# EthernetSwitchBoard.net
KiCad netlist of a schematic drawn in Altium Designer
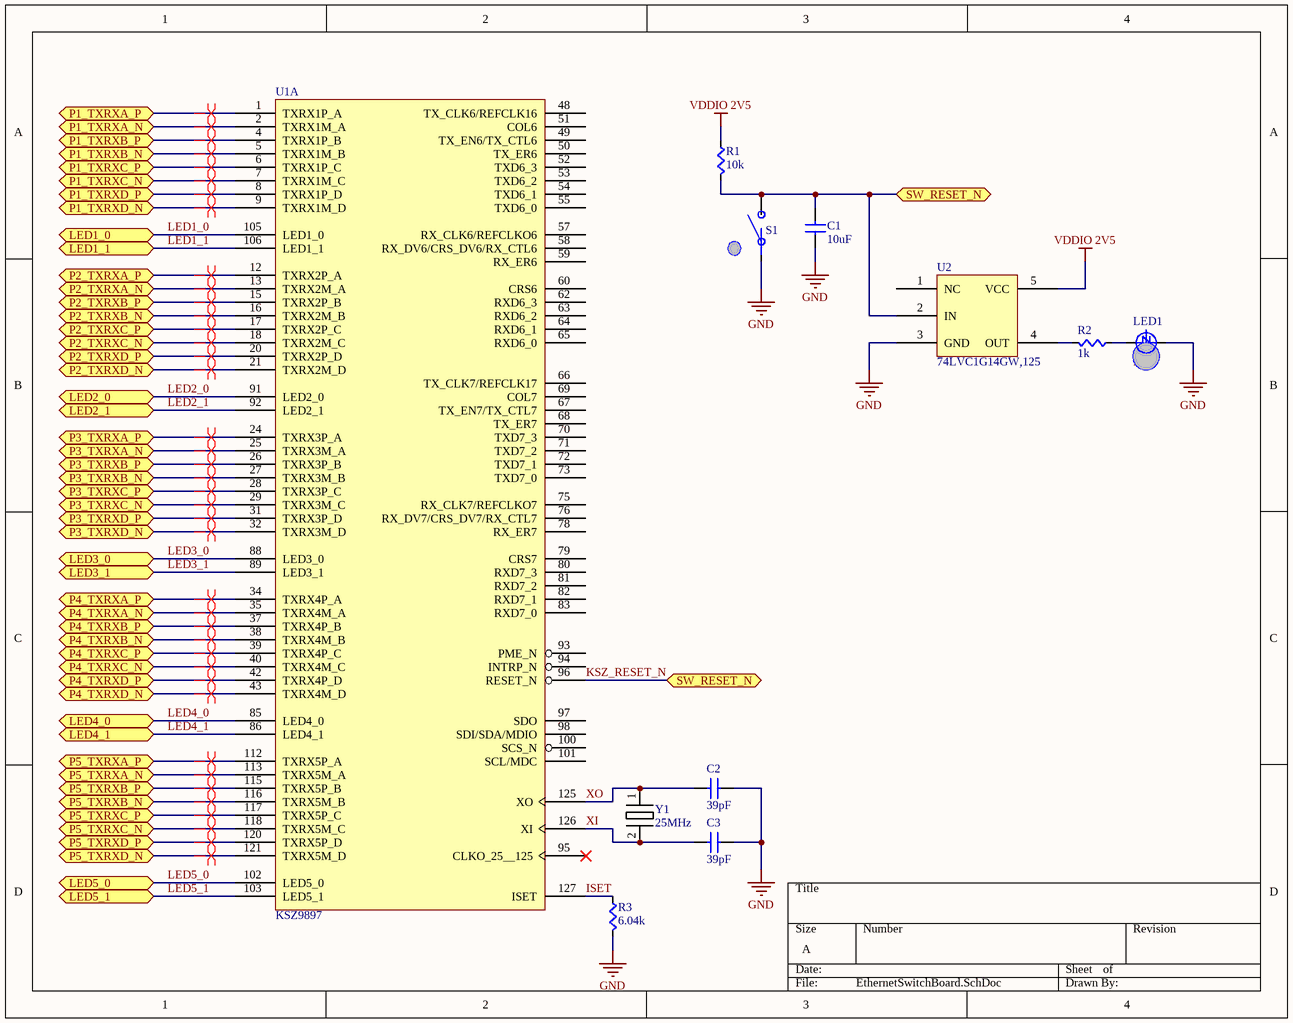
[diagram p0: EthernetSwitchBoard.SchDoc]

(export (version "E")
  (design (tool "Eeschema 10.0.6"))
  (components
    (comp (ref "C1")
      (value "10uF")
      (footprint "CAPC0603")
      (fields (field (name "Comment") "Cap"))
      (libsource (lib "Passives") (part "Cap"))
    )
    (comp (ref "C2")
      (value "39pF")
      (footprint "CAPC0603")
      (description "CAP CER 39PF 100V C0G/NP0 0603")
      (fields (field (name "Comment") "Cap"))
      (libsource (lib "Passives") (part "Cap"))
    )
    (comp (ref "C3")
      (value "39pF")
      (footprint "CAPC0603")
      (description "CAP CER 39PF 100V C0G/NP0 0603")
      (fields (field (name "Comment") "Cap"))
      (libsource (lib "Passives") (part "Cap"))
    )
    (comp (ref "LED1")
      (value "LED")
      (footprint "LED0603")
      (fields (field (name "COLOR") "Red"))
      (libsource (lib "Semiconductors") (part "LED"))
    )
    (comp (ref "R1")
      (value "10k")
      (footprint "RES0603")
      (fields (field (name "Comment") "Res"))
      (libsource (lib "Passives") (part "Res"))
    )
    (comp (ref "R2")
      (value "1k")
      (footprint "RES0603")
      (fields (field (name "Comment") "Res"))
      (libsource (lib "Passives") (part "Res"))
    )
    (comp (ref "R3")
      (value "6.04k")
      (footprint "RES0603")
      (fields (field (name "Comment") "Res"))
      (libsource (lib "Passives") (part "Res"))
    )
    (comp (ref "S1")
      (value "Button")
      (footprint "PTS645xxxxSMTR92")
      (description "SPST Button")
      (libsource (lib "Passives") (part "Button"))
    )
    (comp (ref "U1")
      (value "KSZ9897")
      (footprint "ICs:128-TQFP")
      (description "Ethernet Switch 10/100/1000 Base-T PHY I²C, SPI Interface 128-TQFP (14x14)")
      (libsource (lib "ICs") (part "KSZ9897RTXC-TR"))
    )
    (comp (ref "U2")
      (value "74LVC1G14GW,125")
      (footprint "ICs:SOT35-5pin")
      (description "IC SCHMITT-TRIG INV 5TSSOP")
      (libsource (lib "ICs") (part "74LVC1G14GW,125"))
    )
    (comp (ref "Y1")
      (value "25MHz")
      (footprint "ICs:HC49/US")
      (description "25MHz ±30ppm Crystal 18pF 40 Ohm -20°C ~ 70°C Surface Mount HC49/US")
      (libsource (lib "ICs") (part "ABLS-25.000MHZ-B4-F-T"))
    )
  )
  (nets
    (net (code "1") (name "/ISET") (class "Default")
      (node (ref "R3") (pin "2") (pinfunction "B_2") (pintype "passive"))
      (node (ref "U1") (pin "127") (pinfunction "ISET_127") (pintype "passive"))
    )
    (net (code "2") (name "/KSZ_RESET_N") (class "Default")
      (node (ref "C1") (pin "1") (pinfunction "A_1") (pintype "passive"))
      (node (ref "R1") (pin "1") (pinfunction "A_1") (pintype "passive"))
      (node (ref "S1") (pin "B") (pinfunction "B_B") (pintype "passive"))
      (node (ref "U1") (pin "96") (pinfunction "RESET_N_96") (pintype "passive"))
      (node (ref "U2") (pin "2") (pinfunction "IN_2") (pintype "passive"))
    )
    (net (code "3") (name "/LED1_0") (class "Default")
      (node (ref "U1") (pin "105") (pinfunction "LED1_0_105") (pintype "passive"))
    )
    (net (code "4") (name "/LED1_1") (class "Default")
      (node (ref "U1") (pin "106") (pinfunction "LED1_1_106") (pintype "passive"))
    )
    (net (code "5") (name "/LED2_0") (class "Default")
      (node (ref "U1") (pin "91") (pinfunction "LED2_0_91") (pintype "passive"))
    )
    (net (code "6") (name "/LED2_1") (class "Default")
      (node (ref "U1") (pin "92") (pinfunction "LED2_1_92") (pintype "passive"))
    )
    (net (code "7") (name "/LED3_0") (class "Default")
      (node (ref "U1") (pin "88") (pinfunction "LED3_0_88") (pintype "passive"))
    )
    (net (code "8") (name "/LED3_1") (class "Default")
      (node (ref "U1") (pin "89") (pinfunction "LED3_1_89") (pintype "passive"))
    )
    (net (code "9") (name "/LED4_0") (class "Default")
      (node (ref "U1") (pin "85") (pinfunction "LED4_0_85") (pintype "passive"))
    )
    (net (code "10") (name "/LED4_1") (class "Default")
      (node (ref "U1") (pin "86") (pinfunction "LED4_1_86") (pintype "passive"))
    )
    (net (code "11") (name "/LED5_0") (class "Default")
      (node (ref "U1") (pin "102") (pinfunction "LED5_0_102") (pintype "passive"))
    )
    (net (code "12") (name "/LED5_1") (class "Default")
      (node (ref "U1") (pin "103") (pinfunction "LED5_1_103") (pintype "passive"))
    )
    (net (code "13") (name "/P1_TXRXA_N") (class "Default")
      (node (ref "U1") (pin "2") (pinfunction "TXRX1M_A_2") (pintype "passive"))
    )
    (net (code "14") (name "/P1_TXRXA_P") (class "Default")
      (node (ref "U1") (pin "1") (pinfunction "TXRX1P_A_1") (pintype "passive"))
    )
    (net (code "15") (name "/P1_TXRXB_N") (class "Default")
      (node (ref "U1") (pin "5") (pinfunction "TXRX1M_B_5") (pintype "passive"))
    )
    (net (code "16") (name "/P1_TXRXB_P") (class "Default")
      (node (ref "U1") (pin "4") (pinfunction "TXRX1P_B_4") (pintype "passive"))
    )
    (net (code "17") (name "/P1_TXRXC_N") (class "Default")
      (node (ref "U1") (pin "7") (pinfunction "TXRX1M_C_7") (pintype "passive"))
    )
    (net (code "18") (name "/P1_TXRXC_P") (class "Default")
      (node (ref "U1") (pin "6") (pinfunction "TXRX1P_C_6") (pintype "passive"))
    )
    (net (code "19") (name "/P1_TXRXD_N") (class "Default")
      (node (ref "U1") (pin "9") (pinfunction "TXRX1M_D_9") (pintype "passive"))
    )
    (net (code "20") (name "/P1_TXRXD_P") (class "Default")
      (node (ref "U1") (pin "8") (pinfunction "TXRX1P_D_8") (pintype "passive"))
    )
    (net (code "21") (name "/P2_TXRXA_N") (class "Default")
      (node (ref "U1") (pin "13") (pinfunction "TXRX2M_A_13") (pintype "passive"))
    )
    (net (code "22") (name "/P2_TXRXA_P") (class "Default")
      (node (ref "U1") (pin "12") (pinfunction "TXRX2P_A_12") (pintype "passive"))
    )
    (net (code "23") (name "/P2_TXRXB_N") (class "Default")
      (node (ref "U1") (pin "16") (pinfunction "TXRX2M_B_16") (pintype "passive"))
    )
    (net (code "24") (name "/P2_TXRXB_P") (class "Default")
      (node (ref "U1") (pin "15") (pinfunction "TXRX2P_B_15") (pintype "passive"))
    )
    (net (code "25") (name "/P2_TXRXC_N") (class "Default")
      (node (ref "U1") (pin "18") (pinfunction "TXRX2M_C_18") (pintype "passive"))
    )
    (net (code "26") (name "/P2_TXRXC_P") (class "Default")
      (node (ref "U1") (pin "17") (pinfunction "TXRX2P_C_17") (pintype "passive"))
    )
    (net (code "27") (name "/P2_TXRXD_N") (class "Default")
      (node (ref "U1") (pin "21") (pinfunction "TXRX2M_D_21") (pintype "passive"))
    )
    (net (code "28") (name "/P2_TXRXD_P") (class "Default")
      (node (ref "U1") (pin "20") (pinfunction "TXRX2P_D_20") (pintype "passive"))
    )
    (net (code "29") (name "/P3_TXRXA_N") (class "Default")
      (node (ref "U1") (pin "25") (pinfunction "TXRX3M_A_25") (pintype "passive"))
    )
    (net (code "30") (name "/P3_TXRXA_P") (class "Default")
      (node (ref "U1") (pin "24") (pinfunction "TXRX3P_A_24") (pintype "passive"))
    )
    (net (code "31") (name "/P3_TXRXB_N") (class "Default")
      (node (ref "U1") (pin "27") (pinfunction "TXRX3M_B_27") (pintype "passive"))
    )
    (net (code "32") (name "/P3_TXRXB_P") (class "Default")
      (node (ref "U1") (pin "26") (pinfunction "TXRX3P_B_26") (pintype "passive"))
    )
    (net (code "33") (name "/P3_TXRXC_N") (class "Default")
      (node (ref "U1") (pin "29") (pinfunction "TXRX3M_C_29") (pintype "passive"))
    )
    (net (code "34") (name "/P3_TXRXC_P") (class "Default")
      (node (ref "U1") (pin "28") (pinfunction "TXRX3P_C_28") (pintype "passive"))
    )
    (net (code "35") (name "/P3_TXRXD_N") (class "Default")
      (node (ref "U1") (pin "32") (pinfunction "TXRX3M_D_32") (pintype "passive"))
    )
    (net (code "36") (name "/P3_TXRXD_P") (class "Default")
      (node (ref "U1") (pin "31") (pinfunction "TXRX3P_D_31") (pintype "passive"))
    )
    (net (code "37") (name "/P4_TXRXA_N") (class "Default")
      (node (ref "U1") (pin "35") (pinfunction "TXRX4M_A_35") (pintype "passive"))
    )
    (net (code "38") (name "/P4_TXRXA_P") (class "Default")
      (node (ref "U1") (pin "34") (pinfunction "TXRX4P_A_34") (pintype "passive"))
    )
    (net (code "39") (name "/P4_TXRXB_N") (class "Default")
      (node (ref "U1") (pin "38") (pinfunction "TXRX4M_B_38") (pintype "passive"))
    )
    (net (code "40") (name "/P4_TXRXB_P") (class "Default")
      (node (ref "U1") (pin "37") (pinfunction "TXRX4P_B_37") (pintype "passive"))
    )
    (net (code "41") (name "/P4_TXRXC_N") (class "Default")
      (node (ref "U1") (pin "40") (pinfunction "TXRX4M_C_40") (pintype "passive"))
    )
    (net (code "42") (name "/P4_TXRXC_P") (class "Default")
      (node (ref "U1") (pin "39") (pinfunction "TXRX4P_C_39") (pintype "passive"))
    )
    (net (code "43") (name "/P4_TXRXD_N") (class "Default")
      (node (ref "U1") (pin "43") (pinfunction "TXRX4M_D_43") (pintype "passive"))
    )
    (net (code "44") (name "/P4_TXRXD_P") (class "Default")
      (node (ref "U1") (pin "42") (pinfunction "TXRX4P_D_42") (pintype "passive"))
    )
    (net (code "45") (name "/P5_TXRXA_N") (class "Default")
      (node (ref "U1") (pin "113") (pinfunction "TXRX5M_A_113") (pintype "passive"))
    )
    (net (code "46") (name "/P5_TXRXA_P") (class "Default")
      (node (ref "U1") (pin "112") (pinfunction "TXRX5P_A_112") (pintype "passive"))
    )
    (net (code "47") (name "/P5_TXRXB_N") (class "Default")
      (node (ref "U1") (pin "116") (pinfunction "TXRX5M_B_116") (pintype "passive"))
    )
    (net (code "48") (name "/P5_TXRXB_P") (class "Default")
      (node (ref "U1") (pin "115") (pinfunction "TXRX5P_B_115") (pintype "passive"))
    )
    (net (code "49") (name "/P5_TXRXC_N") (class "Default")
      (node (ref "U1") (pin "118") (pinfunction "TXRX5M_C_118") (pintype "passive"))
    )
    (net (code "50") (name "/P5_TXRXC_P") (class "Default")
      (node (ref "U1") (pin "117") (pinfunction "TXRX5P_C_117") (pintype "passive"))
    )
    (net (code "51") (name "/P5_TXRXD_N") (class "Default")
      (node (ref "U1") (pin "121") (pinfunction "TXRX5M_D_121") (pintype "passive"))
    )
    (net (code "52") (name "/P5_TXRXD_P") (class "Default")
      (node (ref "U1") (pin "120") (pinfunction "TXRX5P_D_120") (pintype "passive"))
    )
    (net (code "53") (name "/XI") (class "Default")
      (node (ref "C3") (pin "1") (pinfunction "A_1") (pintype "passive"))
      (node (ref "U1") (pin "126") (pinfunction "XI_126") (pintype "passive"))
      (node (ref "Y1") (pin "2") (pinfunction "2_2") (pintype "passive"))
    )
    (net (code "54") (name "/XO") (class "Default")
      (node (ref "C2") (pin "1") (pinfunction "A_1") (pintype "passive"))
      (node (ref "U1") (pin "125") (pinfunction "XO_125") (pintype "passive"))
      (node (ref "Y1") (pin "1") (pinfunction "1_1") (pintype "passive"))
    )
    (net (code "55") (name "GND") (class "Default")
      (node (ref "C1") (pin "2") (pinfunction "B_2") (pintype "passive"))
      (node (ref "C2") (pin "2") (pinfunction "B_2") (pintype "passive"))
      (node (ref "C3") (pin "2") (pinfunction "B_2") (pintype "passive"))
      (node (ref "LED1") (pin "C") (pinfunction "C_C") (pintype "passive"))
      (node (ref "R3") (pin "1") (pinfunction "A_1") (pintype "passive"))
      (node (ref "S1") (pin "A") (pinfunction "A_A") (pintype "passive"))
      (node (ref "U2") (pin "3") (pinfunction "GND_3") (pintype "passive"))
    )
    (net (code "56") (name "Net-(R2-A)") (class "Default")
      (node (ref "R2") (pin "1") (pinfunction "A_1") (pintype "passive"))
      (node (ref "U2") (pin "4") (pinfunction "OUT_4") (pintype "passive"))
    )
    (net (code "57") (name "Net-(R2-B)") (class "Default")
      (node (ref "LED1") (pin "A") (pinfunction "A_A") (pintype "passive"))
      (node (ref "R2") (pin "2") (pinfunction "B_2") (pintype "passive"))
    )
    (net (code "58") (name "VDDIO 2V5") (class "Default")
      (node (ref "R1") (pin "2") (pinfunction "B_2") (pintype "passive"))
      (node (ref "U2") (pin "5") (pinfunction "VCC_5") (pintype "passive"))
    )
    (net (code "59") (name "unconnected-(U1A-CLKO_25__125-Pad95)") (class "Default")
      (node (ref "U1") (pin "95") (pinfunction "CLKO_25__125_95") (pintype "passive+no_connect"))
    )
    (net (code "60") (name "unconnected-(U1A-COL6-Pad51)") (class "Default")
      (node (ref "U1") (pin "51") (pinfunction "COL6_51") (pintype "passive"))
    )
    (net (code "61") (name "unconnected-(U1A-COL7-Pad69)") (class "Default")
      (node (ref "U1") (pin "69") (pinfunction "COL7_69") (pintype "passive"))
    )
    (net (code "62") (name "unconnected-(U1A-CRS6-Pad60)") (class "Default")
      (node (ref "U1") (pin "60") (pinfunction "CRS6_60") (pintype "passive"))
    )
    (net (code "63") (name "unconnected-(U1A-CRS7-Pad79)") (class "Default")
      (node (ref "U1") (pin "79") (pinfunction "CRS7_79") (pintype "passive"))
    )
    (net (code "64") (name "unconnected-(U1A-INTRP_N-Pad94)") (class "Default")
      (node (ref "U1") (pin "94") (pinfunction "INTRP_N_94") (pintype "passive"))
    )
    (net (code "65") (name "unconnected-(U1A-PME_N-Pad93)") (class "Default")
      (node (ref "U1") (pin "93") (pinfunction "PME_N_93") (pintype "passive"))
    )
    (net (code "66") (name "unconnected-(U1A-RXD6_0-Pad65)") (class "Default")
      (node (ref "U1") (pin "65") (pinfunction "RXD6_0_65") (pintype "passive"))
    )
    (net (code "67") (name "unconnected-(U1A-RXD6_1-Pad64)") (class "Default")
      (node (ref "U1") (pin "64") (pinfunction "RXD6_1_64") (pintype "passive"))
    )
    (net (code "68") (name "unconnected-(U1A-RXD6_2-Pad63)") (class "Default")
      (node (ref "U1") (pin "63") (pinfunction "RXD6_2_63") (pintype "passive"))
    )
    (net (code "69") (name "unconnected-(U1A-RXD6_3-Pad62)") (class "Default")
      (node (ref "U1") (pin "62") (pinfunction "RXD6_3_62") (pintype "passive"))
    )
    (net (code "70") (name "unconnected-(U1A-RXD7_0-Pad83)") (class "Default")
      (node (ref "U1") (pin "83") (pinfunction "RXD7_0_83") (pintype "passive"))
    )
    (net (code "71") (name "unconnected-(U1A-RXD7_1-Pad82)") (class "Default")
      (node (ref "U1") (pin "82") (pinfunction "RXD7_1_82") (pintype "passive"))
    )
    (net (code "72") (name "unconnected-(U1A-RXD7_2-Pad81)") (class "Default")
      (node (ref "U1") (pin "81") (pinfunction "RXD7_2_81") (pintype "passive"))
    )
    (net (code "73") (name "unconnected-(U1A-RXD7_3-Pad80)") (class "Default")
      (node (ref "U1") (pin "80") (pinfunction "RXD7_3_80") (pintype "passive"))
    )
    (net (code "74") (name "unconnected-(U1A-RX_CLK6{slash}REFCLKO6-Pad57)") (class "Default")
      (node (ref "U1") (pin "57") (pinfunction "RX_CLK6/REFCLKO6_57") (pintype "passive"))
    )
    (net (code "75") (name "unconnected-(U1A-RX_CLK7{slash}REFCLKO7-Pad75)") (class "Default")
      (node (ref "U1") (pin "75") (pinfunction "RX_CLK7/REFCLKO7_75") (pintype "passive"))
    )
    (net (code "76") (name "unconnected-(U1A-RX_DV6{slash}CRS_DV6{slash}RX_CTL6-Pad58)") (class "Default")
      (node (ref "U1") (pin "58") (pinfunction "RX_DV6/CRS_DV6/RX_CTL6_58") (pintype "passive"))
    )
    (net (code "77") (name "unconnected-(U1A-RX_DV7{slash}CRS_DV7{slash}RX_CTL7-Pad76)") (class "Default")
      (node (ref "U1") (pin "76") (pinfunction "RX_DV7/CRS_DV7/RX_CTL7_76") (pintype "passive"))
    )
    (net (code "78") (name "unconnected-(U1A-RX_ER6-Pad59)") (class "Default")
      (node (ref "U1") (pin "59") (pinfunction "RX_ER6_59") (pintype "passive"))
    )
    (net (code "79") (name "unconnected-(U1A-RX_ER7-Pad78)") (class "Default")
      (node (ref "U1") (pin "78") (pinfunction "RX_ER7_78") (pintype "passive"))
    )
    (net (code "80") (name "unconnected-(U1A-SCL{slash}MDC-Pad101)") (class "Default")
      (node (ref "U1") (pin "101") (pinfunction "SCL/MDC_101") (pintype "passive"))
    )
    (net (code "81") (name "unconnected-(U1A-SCS_N-Pad100)") (class "Default")
      (node (ref "U1") (pin "100") (pinfunction "SCS_N_100") (pintype "passive"))
    )
    (net (code "82") (name "unconnected-(U1A-SDI{slash}SDA{slash}MDIO-Pad98)") (class "Default")
      (node (ref "U1") (pin "98") (pinfunction "SDI/SDA/MDIO_98") (pintype "passive"))
    )
    (net (code "83") (name "unconnected-(U1A-SDO-Pad97)") (class "Default")
      (node (ref "U1") (pin "97") (pinfunction "SDO_97") (pintype "passive"))
    )
    (net (code "84") (name "unconnected-(U1A-TXD6_0-Pad55)") (class "Default")
      (node (ref "U1") (pin "55") (pinfunction "TXD6_0_55") (pintype "passive"))
    )
    (net (code "85") (name "unconnected-(U1A-TXD6_1-Pad54)") (class "Default")
      (node (ref "U1") (pin "54") (pinfunction "TXD6_1_54") (pintype "passive"))
    )
    (net (code "86") (name "unconnected-(U1A-TXD6_2-Pad53)") (class "Default")
      (node (ref "U1") (pin "53") (pinfunction "TXD6_2_53") (pintype "passive"))
    )
    (net (code "87") (name "unconnected-(U1A-TXD6_3-Pad52)") (class "Default")
      (node (ref "U1") (pin "52") (pinfunction "TXD6_3_52") (pintype "passive"))
    )
    (net (code "88") (name "unconnected-(U1A-TXD7_0-Pad73)") (class "Default")
      (node (ref "U1") (pin "73") (pinfunction "TXD7_0_73") (pintype "passive"))
    )
    (net (code "89") (name "unconnected-(U1A-TXD7_1-Pad72)") (class "Default")
      (node (ref "U1") (pin "72") (pinfunction "TXD7_1_72") (pintype "passive"))
    )
    (net (code "90") (name "unconnected-(U1A-TXD7_2-Pad71)") (class "Default")
      (node (ref "U1") (pin "71") (pinfunction "TXD7_2_71") (pintype "passive"))
    )
    (net (code "91") (name "unconnected-(U1A-TXD7_3-Pad70)") (class "Default")
      (node (ref "U1") (pin "70") (pinfunction "TXD7_3_70") (pintype "passive"))
    )
    (net (code "92") (name "unconnected-(U1A-TX_CLK6{slash}REFCLK16-Pad48)") (class "Default")
      (node (ref "U1") (pin "48") (pinfunction "TX_CLK6/REFCLK16_48") (pintype "passive"))
    )
    (net (code "93") (name "unconnected-(U1A-TX_CLK7{slash}REFCLK17-Pad66)") (class "Default")
      (node (ref "U1") (pin "66") (pinfunction "TX_CLK7/REFCLK17_66") (pintype "passive"))
    )
    (net (code "94") (name "unconnected-(U1A-TX_EN6{slash}TX_CTL6-Pad49)") (class "Default")
      (node (ref "U1") (pin "49") (pinfunction "TX_EN6/TX_CTL6_49") (pintype "passive"))
    )
    (net (code "95") (name "unconnected-(U1A-TX_EN7{slash}TX_CTL7-Pad67)") (class "Default")
      (node (ref "U1") (pin "67") (pinfunction "TX_EN7/TX_CTL7_67") (pintype "passive"))
    )
    (net (code "96") (name "unconnected-(U1A-TX_ER6-Pad50)") (class "Default")
      (node (ref "U1") (pin "50") (pinfunction "TX_ER6_50") (pintype "passive"))
    )
    (net (code "97") (name "unconnected-(U1A-TX_ER7-Pad68)") (class "Default")
      (node (ref "U1") (pin "68") (pinfunction "TX_ER7_68") (pintype "passive"))
    )
    (net (code "98") (name "unconnected-(U2-NC-Pad1)") (class "Default")
      (node (ref "U2") (pin "1") (pinfunction "NC_1") (pintype "passive"))
    )
  )
)
